# Acoustics_Board.net
KiCad netlist of a schematic drawn in Altium Designer
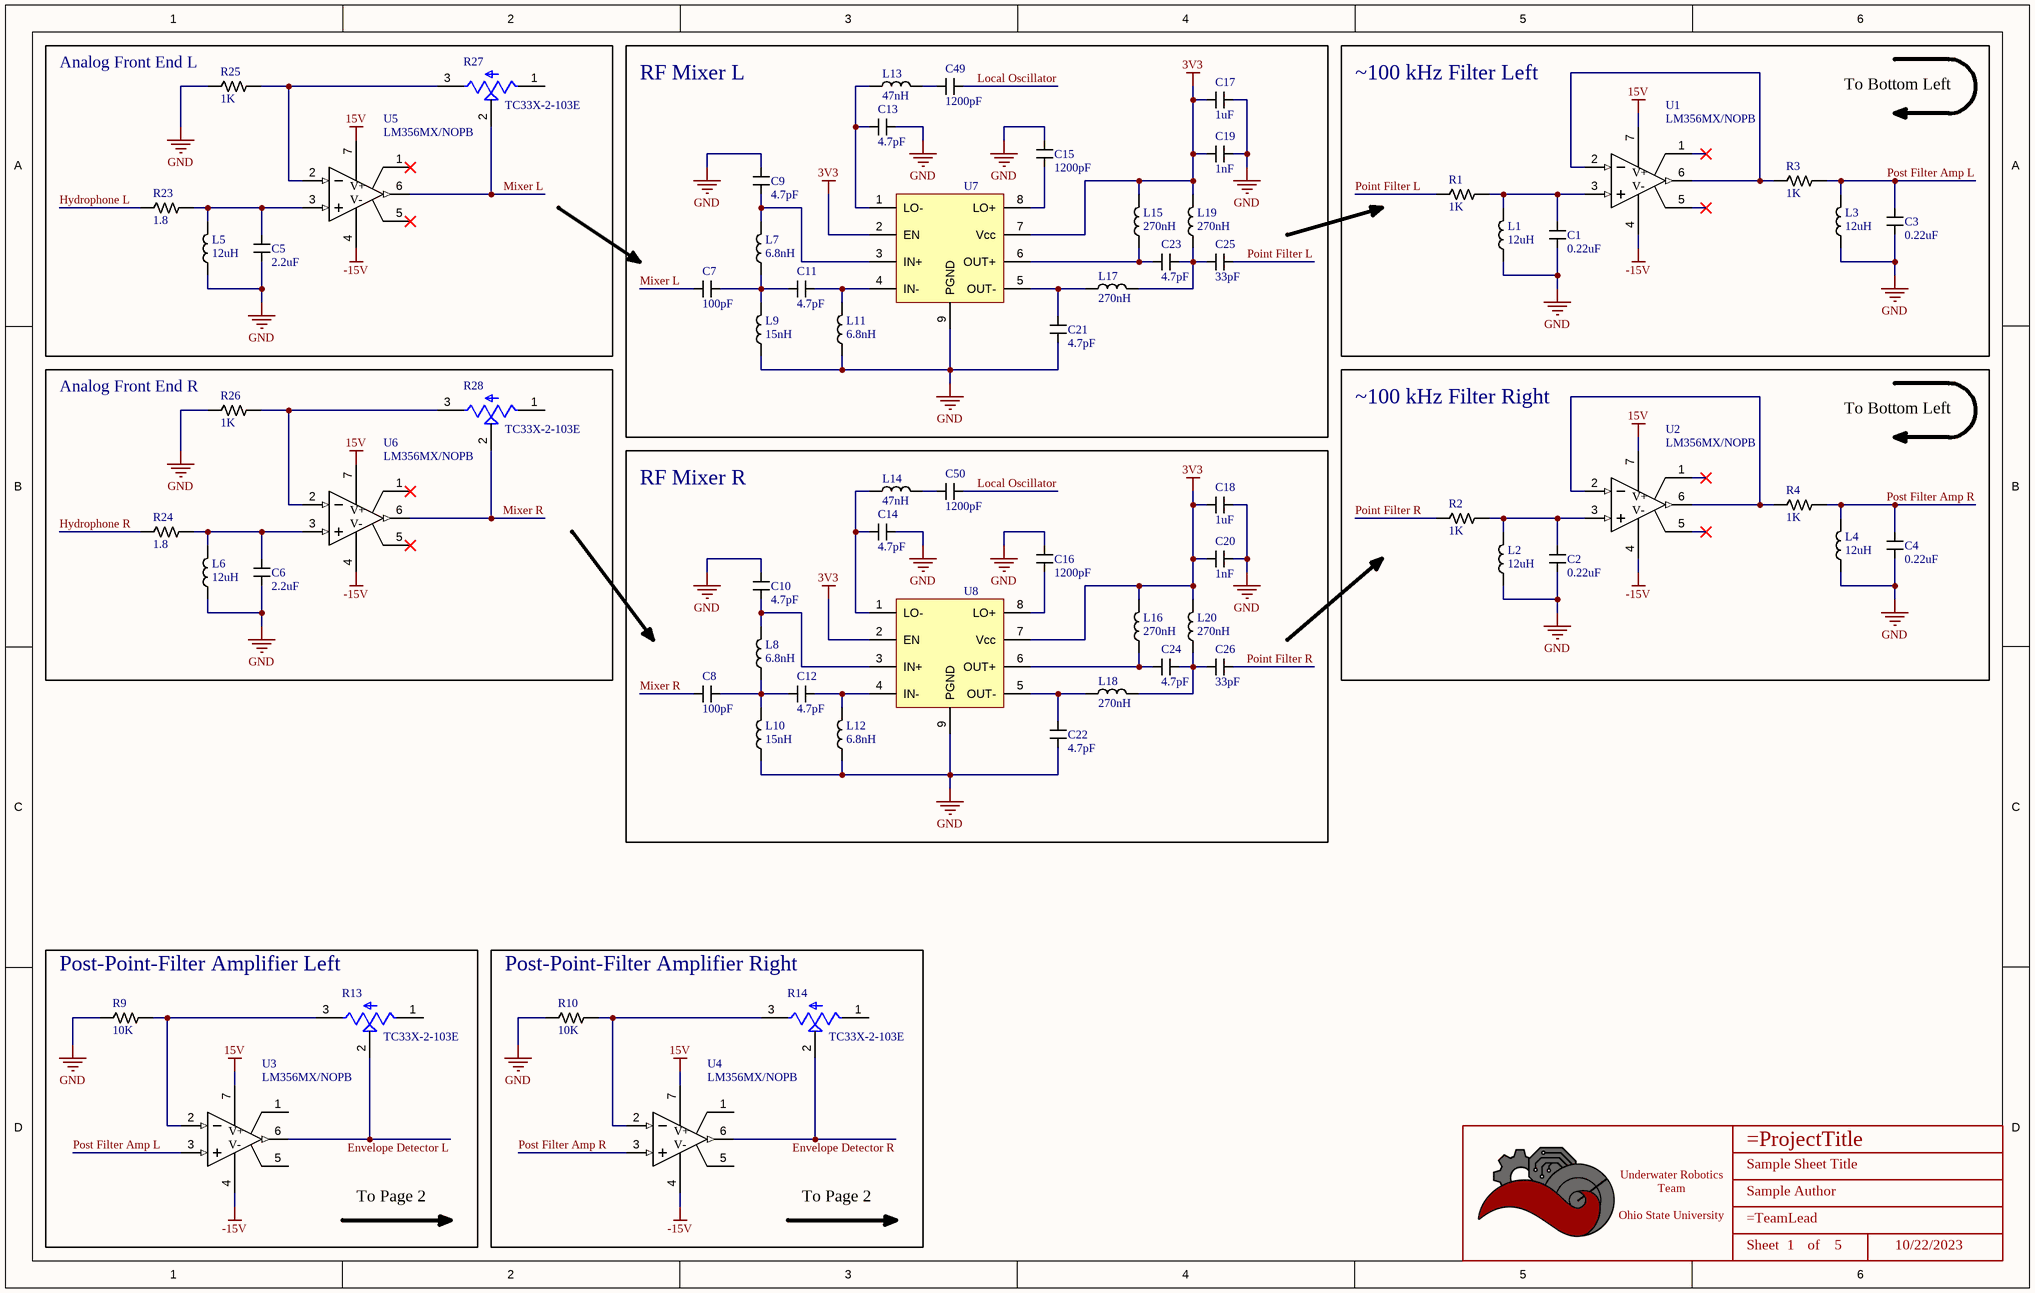
[diagram p0: Acoustics Board.SchDoc]

(export (version "E")
  (design (tool "Eeschema 10.0.6"))
  (components
    (comp (ref "*")
      (value "Title_Block")
      (footprint "LOGO")
      (description "UWRT Schematic Title Block Template\r\n\r\nCreated June 2021, Dylan Trainor")
      (libsource (lib "UWRT") (part "Title_Block"))
    )
    (comp (ref "C1")
      (value "0.22uF")
      (footprint "CAPACITOR_0603")
      (description "CAP CER 0.22uF 16V X7R 0603")
      (fields
        (field (name "TOLERANCE") "+/- 5%")
        (field (name "VOLTAGE") "16V")
        (field (name "MADE BY") "Nathan Ayer")
      )
      (libsource (lib "Capacitors") (part "CAPACITOR_0.000027uF_0603"))
    )
    (comp (ref "C2")
      (value "0.22uF")
      (footprint "CAPACITOR_0603")
      (description "CAP CER 0.22uF 16V X7R 0603")
      (fields
        (field (name "TOLERANCE") "+/- 5%")
        (field (name "VOLTAGE") "16V")
        (field (name "MADE BY") "Nathan Ayer")
      )
      (libsource (lib "Capacitors") (part "CAPACITOR_0.000027uF_0603"))
    )
    (comp (ref "C3")
      (value "0.22uF")
      (footprint "CAPACITOR_0603")
      (description "CAP CER 0.22uF 16V X7R 0603")
      (fields
        (field (name "TOLERANCE") "+/- 5%")
        (field (name "VOLTAGE") "16V")
        (field (name "MADE BY") "Nathan Ayer")
      )
      (libsource (lib "Capacitors") (part "CAPACITOR_0.000027uF_0603"))
    )
    (comp (ref "C4")
      (value "0.22uF")
      (footprint "CAPACITOR_0603")
      (description "CAP CER 0.22uF 16V X7R 0603")
      (fields
        (field (name "TOLERANCE") "+/- 5%")
        (field (name "VOLTAGE") "16V")
        (field (name "MADE BY") "Nathan Ayer")
      )
      (libsource (lib "Capacitors") (part "CAPACITOR_0.000027uF_0603"))
    )
    (comp (ref "C5")
      (value "2.2uF")
      (footprint "CAPACITOR_0603")
      (description "CAP CER 2.2PF 50V C0G/NP0 0603")
      (fields
        (field (name "TOLERANCE") "+/- 20%")
        (field (name "VOLTAGE") "6.3V")
        (field (name "MADE BY") "Flip B")
      )
      (libsource (lib "Capacitors") (part "CAPACITOR_22uF_0603"))
    )
    (comp (ref "C6")
      (value "2.2uF")
      (footprint "CAPACITOR_0603")
      (description "CAP CER 2.2PF 50V C0G/NP0 0603")
      (fields
        (field (name "TOLERANCE") "+/- 20%")
        (field (name "VOLTAGE") "6.3V")
        (field (name "MADE BY") "Flip B")
      )
      (libsource (lib "Capacitors") (part "CAPACITOR_22uF_0603"))
    )
    (comp (ref "C7")
      (value "100pF")
      (footprint "CAPACITOR_0402")
      (description "Cap 100pF 25V +/-10%\r\nCeramic 0402")
      (fields
        (field (name "TOLERANCE") "+/- 10%")
        (field (name "VOLTAGE") "25V")
        (field (name "MADE BY") "Robert Pafford")
      )
      (libsource (lib "Capacitors") (part "CAPACITOR_0.0001uF_0402"))
    )
    (comp (ref "C8")
      (value "100pF")
      (footprint "CAPACITOR_0402")
      (description "Cap 100pF 25V +/-10%\r\nCeramic 0402")
      (fields
        (field (name "TOLERANCE") "+/- 10%")
        (field (name "VOLTAGE") "25V")
        (field (name "MADE BY") "Robert Pafford")
      )
      (libsource (lib "Capacitors") (part "CAPACITOR_0.0001uF_0402"))
    )
    (comp (ref "C9")
      (value "4.7pF")
      (footprint "CAPACITOR_0402")
      (description "4.7 pF ±0.1pF 50V Ceramic Capacitor C0G, NP0 0402 (1005 Metric)")
      (fields (field (name "TOLERANCE") "+/- 0.1 pF") (field (name "VOLTAGE") "50V"))
      (libsource (lib "Capacitors") (part "CAPACITOR_0.000015uF_0402"))
    )
    (comp (ref "C10")
      (value "4.7pF")
      (footprint "CAPACITOR_0402")
      (description "4.7 pF ±0.1pF 50V Ceramic Capacitor C0G, NP0 0402 (1005 Metric)")
      (fields (field (name "TOLERANCE") "+/- 0.1 pF") (field (name "VOLTAGE") "50V"))
      (libsource (lib "Capacitors") (part "CAPACITOR_0.000015uF_0402"))
    )
    (comp (ref "C11")
      (value "4.7pF")
      (footprint "CAPACITOR_0402")
      (description "4.7 pF ±0.1pF 50V Ceramic Capacitor C0G, NP0 0402 (1005 Metric)")
      (fields (field (name "TOLERANCE") "+/- 0.1 pF") (field (name "VOLTAGE") "50V"))
      (libsource (lib "Capacitors") (part "CAPACITOR_0.000015uF_0402"))
    )
    (comp (ref "C12")
      (value "4.7pF")
      (footprint "CAPACITOR_0402")
      (description "4.7 pF ±0.1pF 50V Ceramic Capacitor C0G, NP0 0402 (1005 Metric)")
      (fields (field (name "TOLERANCE") "+/- 0.1 pF") (field (name "VOLTAGE") "50V"))
      (libsource (lib "Capacitors") (part "CAPACITOR_0.000015uF_0402"))
    )
    (comp (ref "C13")
      (value "4.7pF")
      (footprint "CAPACITOR_0402")
      (description "4.7 pF ±0.1pF 50V Ceramic Capacitor C0G, NP0 0402 (1005 Metric)")
      (fields (field (name "TOLERANCE") "+/- 0.1 pF") (field (name "VOLTAGE") "50V"))
      (libsource (lib "Capacitors") (part "CAPACITOR_0.000015uF_0402"))
    )
    (comp (ref "C14")
      (value "4.7pF")
      (footprint "CAPACITOR_0402")
      (description "4.7 pF ±0.1pF 50V Ceramic Capacitor C0G, NP0 0402 (1005 Metric)")
      (fields (field (name "TOLERANCE") "+/- 0.1 pF") (field (name "VOLTAGE") "50V"))
      (libsource (lib "Capacitors") (part "CAPACITOR_0.000015uF_0402"))
    )
    (comp (ref "C15")
      (value "1200pF")
      (footprint "CAPACITOR_0402")
      (description "CAP CER 1200PF 50V X7R 0402")
      (fields
        (field (name "TOLERANCE") "+/- 5%")
        (field (name "VOLTAGE") "50V")
        (field (name "MADE BY") "Robert Pafford")
      )
      (libsource (lib "Capacitors") (part "CAPACITOR_0.0012uF_0402"))
    )
    (comp (ref "C16")
      (value "1200pF")
      (footprint "CAPACITOR_0402")
      (description "CAP CER 1200PF 50V X7R 0402")
      (fields
        (field (name "TOLERANCE") "+/- 5%")
        (field (name "VOLTAGE") "50V")
        (field (name "MADE BY") "Robert Pafford")
      )
      (libsource (lib "Capacitors") (part "CAPACITOR_0.0012uF_0402"))
    )
    (comp (ref "C17")
      (value "1uF")
      (footprint "CAPACITOR_0603")
      (description "Cap 1uF 25V +/-10%\r\nCeramic 0603")
      (fields
        (field (name "TOLERANCE") "+/- 10%")
        (field (name "VOLTAGE") "16V")
        (field (name "MADE BY") "Flip B")
      )
      (libsource (lib "Capacitors") (part "CAPACITOR_1uF_0603_25V"))
    )
    (comp (ref "C18")
      (value "1uF")
      (footprint "CAPACITOR_0603")
      (description "Cap 1uF 25V +/-10%\r\nCeramic 0603")
      (fields
        (field (name "TOLERANCE") "+/- 10%")
        (field (name "VOLTAGE") "16V")
        (field (name "MADE BY") "Flip B")
      )
      (libsource (lib "Capacitors") (part "CAPACITOR_1uF_0603_25V"))
    )
    (comp (ref "C19")
      (value "1nF")
      (footprint "CAPACITOR_0603")
      (description "Cap 1000pF 50V +/-2%\r\nCeramic 0603")
      (fields
        (field (name "TOLERANCE") "+/- 2%")
        (field (name "VOLTAGE") "50")
        (field (name "MADE BY") "Flip B")
      )
      (libsource (lib "Capacitors") (part "CAPACITOR_0.001uF_0603"))
    )
    (comp (ref "C20")
      (value "1nF")
      (footprint "CAPACITOR_0603")
      (description "Cap 1000pF 50V +/-2%\r\nCeramic 0603")
      (fields
        (field (name "TOLERANCE") "+/- 2%")
        (field (name "VOLTAGE") "50")
        (field (name "MADE BY") "Flip B")
      )
      (libsource (lib "Capacitors") (part "CAPACITOR_0.001uF_0603"))
    )
    (comp (ref "C21")
      (value "4.7pF")
      (footprint "CAPACITOR_0402")
      (description "4.7 pF ±0.1pF 50V Ceramic Capacitor C0G, NP0 0402 (1005 Metric)")
      (fields (field (name "TOLERANCE") "+/- 0.1 pF") (field (name "VOLTAGE") "50V"))
      (libsource (lib "Capacitors") (part "CAPACITOR_0.000015uF_0402"))
    )
    (comp (ref "C22")
      (value "4.7pF")
      (footprint "CAPACITOR_0402")
      (description "4.7 pF ±0.1pF 50V Ceramic Capacitor C0G, NP0 0402 (1005 Metric)")
      (fields (field (name "TOLERANCE") "+/- 0.1 pF") (field (name "VOLTAGE") "50V"))
      (libsource (lib "Capacitors") (part "CAPACITOR_0.000015uF_0402"))
    )
    (comp (ref "C23")
      (value "4.7pF")
      (footprint "CAPACITOR_0402")
      (description "4.7 pF ±0.1pF 50V Ceramic Capacitor C0G, NP0 0402 (1005 Metric)")
      (fields (field (name "TOLERANCE") "+/- 0.1 pF") (field (name "VOLTAGE") "50V"))
      (libsource (lib "Capacitors") (part "CAPACITOR_0.000015uF_0402"))
    )
    (comp (ref "C24")
      (value "4.7pF")
      (footprint "CAPACITOR_0402")
      (description "4.7 pF ±0.1pF 50V Ceramic Capacitor C0G, NP0 0402 (1005 Metric)")
      (fields (field (name "TOLERANCE") "+/- 0.1 pF") (field (name "VOLTAGE") "50V"))
      (libsource (lib "Capacitors") (part "CAPACITOR_0.000015uF_0402"))
    )
    (comp (ref "C25")
      (value "33pF")
      (footprint "CAPACITOR_0603")
      (description "33 pF ±5% 250V Ceramic Capacitor C0G, NP0 0603 (1608 Metric)")
      (fields (field (name "TOLERANCE") "+/- 5%") (field (name "VOLTAGE") "250V"))
      (libsource (lib "Capacitors") (part "CAPACITOR_0.001uF_0603"))
    )
    (comp (ref "C26")
      (value "33pF")
      (footprint "CAPACITOR_0603")
      (description "33 pF ±5% 250V Ceramic Capacitor C0G, NP0 0603 (1608 Metric)")
      (fields (field (name "TOLERANCE") "+/- 5%") (field (name "VOLTAGE") "250V"))
      (libsource (lib "Capacitors") (part "CAPACITOR_0.001uF_0603"))
    )
    (comp (ref "C49")
      (value "1200pF")
      (footprint "CAPACITOR_0402")
      (description "CAP CER 1200PF 50V X7R 0402")
      (fields
        (field (name "TOLERANCE") "+/- 5%")
        (field (name "VOLTAGE") "50V")
        (field (name "MADE BY") "Robert Pafford")
      )
      (libsource (lib "Capacitors") (part "CAPACITOR_0.0012uF_0402"))
    )
    (comp (ref "C50")
      (value "1200pF")
      (footprint "CAPACITOR_0402")
      (description "CAP CER 1200PF 50V X7R 0402")
      (fields
        (field (name "TOLERANCE") "+/- 5%")
        (field (name "VOLTAGE") "50V")
        (field (name "MADE BY") "Robert Pafford")
      )
      (libsource (lib "Capacitors") (part "CAPACITOR_0.0012uF_0402"))
    )
    (comp (ref "L1")
      (value "12uH")
      (footprint "INDUCTOR_0603")
      (description "12 µH Shielded Multilayer Inductor 10 mA 1.8Ohm Max 0603 (1608 Metric)")
      (fields
        (field (name "TOLERANCE") "+/- 5%")
        (field (name "Comment") "FIXED IND 12UH 10MA 1.8 OHM SMD")
        (field (name "MADE BY") "Nathan Ayer")
      )
      (libsource (lib "Inductors") (part "INDUCTOR_12uH_0603"))
    )
    (comp (ref "L2")
      (value "12uH")
      (footprint "INDUCTOR_0603")
      (description "12 µH Shielded Multilayer Inductor 10 mA 1.8Ohm Max 0603 (1608 Metric)")
      (fields
        (field (name "TOLERANCE") "+/- 5%")
        (field (name "Comment") "FIXED IND 12UH 10MA 1.8 OHM SMD")
        (field (name "MADE BY") "Nathan Ayer")
      )
      (libsource (lib "Inductors") (part "INDUCTOR_12uH_0603"))
    )
    (comp (ref "L3")
      (value "12uH")
      (footprint "INDUCTOR_0603")
      (description "12 µH Shielded Multilayer Inductor 10 mA 1.8Ohm Max 0603 (1608 Metric)")
      (fields
        (field (name "TOLERANCE") "+/- 5%")
        (field (name "Comment") "FIXED IND 12UH 10MA 1.8 OHM SMD")
        (field (name "MADE BY") "Nathan Ayer")
      )
      (libsource (lib "Inductors") (part "INDUCTOR_12uH_0603"))
    )
    (comp (ref "L4")
      (value "12uH")
      (footprint "INDUCTOR_0603")
      (description "12 µH Shielded Multilayer Inductor 10 mA 1.8Ohm Max 0603 (1608 Metric)")
      (fields
        (field (name "TOLERANCE") "+/- 5%")
        (field (name "Comment") "FIXED IND 12UH 10MA 1.8 OHM SMD")
        (field (name "MADE BY") "Nathan Ayer")
      )
      (libsource (lib "Inductors") (part "INDUCTOR_12uH_0603"))
    )
    (comp (ref "L5")
      (value "12uH")
      (footprint "INDUCTOR_0603")
      (description "12 µH Shielded Multilayer Inductor 10 mA 1.8Ohm Max 0603 (1608 Metric)")
      (fields
        (field (name "TOLERANCE") "+/- 20%")
        (field (name "Comment") "FIXED IND 12UH 10MA 1.8 OHM SMD")
        (field (name "MADE BY") "Robert Pafford")
      )
      (libsource (lib "Inductors") (part "INDUCTOR_12uH_0603"))
    )
    (comp (ref "L6")
      (value "12uH")
      (footprint "INDUCTOR_0603")
      (description "12 µH Shielded Multilayer Inductor 10 mA 1.8Ohm Max 0603 (1608 Metric)")
      (fields
        (field (name "TOLERANCE") "+/- 20%")
        (field (name "Comment") "FIXED IND 12UH 10MA 1.8 OHM SMD")
        (field (name "MADE BY") "Robert Pafford")
      )
      (libsource (lib "Inductors") (part "INDUCTOR_12uH_0603"))
    )
    (comp (ref "L7")
      (value "6.8nH")
      (footprint "INDUCTOR_0402")
      (description "6.8 nH Unshielded Multilayer Inductor 250 mA 320mOhm Max 0402 (1005 Metric)")
      (fields (field (name "TOLERANCE") "+/- 5%") (field (name "Comment") "FIXED IND 6.8NH 250MA 320MOHM SM"))
      (libsource (lib "Inductors") (part "INDUCTOR_15nH_0402"))
    )
    (comp (ref "L8")
      (value "6.8nH")
      (footprint "INDUCTOR_0402")
      (description "6.8 nH Unshielded Multilayer Inductor 250 mA 320mOhm Max 0402 (1005 Metric)")
      (fields (field (name "TOLERANCE") "+/- 5%") (field (name "Comment") "FIXED IND 6.8NH 250MA 320MOHM SM"))
      (libsource (lib "Inductors") (part "INDUCTOR_15nH_0402"))
    )
    (comp (ref "L9")
      (value "15nH")
      (footprint "INDUCTOR_0402")
      (description "15 nH Unshielded Multilayer Inductor 250 mA 600mOhm Max 0402 (1005 Metric)")
      (fields (field (name "TOLERANCE") "+/- 5%") (field (name "Comment") "FIXED IND 15NH 250MA 600MOHM SMD"))
      (libsource (lib "Inductors") (part "INDUCTOR_15nH_0402"))
    )
    (comp (ref "L10")
      (value "15nH")
      (footprint "INDUCTOR_0402")
      (description "15 nH Unshielded Multilayer Inductor 250 mA 600mOhm Max 0402 (1005 Metric)")
      (fields (field (name "TOLERANCE") "+/- 5%") (field (name "Comment") "FIXED IND 15NH 250MA 600MOHM SMD"))
      (libsource (lib "Inductors") (part "INDUCTOR_15nH_0402"))
    )
    (comp (ref "L11")
      (value "6.8nH")
      (footprint "INDUCTOR_0402")
      (description "6.8 nH Unshielded Multilayer Inductor 250 mA 320mOhm Max 0402 (1005 Metric)")
      (fields (field (name "TOLERANCE") "+/- 5%") (field (name "Comment") "FIXED IND 6.8NH 250MA 320MOHM SM"))
      (libsource (lib "Inductors") (part "INDUCTOR_15nH_0402"))
    )
    (comp (ref "L12")
      (value "6.8nH")
      (footprint "INDUCTOR_0402")
      (description "6.8 nH Unshielded Multilayer Inductor 250 mA 320mOhm Max 0402 (1005 Metric)")
      (fields (field (name "TOLERANCE") "+/- 5%") (field (name "Comment") "FIXED IND 6.8NH 250MA 320MOHM SM"))
      (libsource (lib "Inductors") (part "INDUCTOR_15nH_0402"))
    )
    (comp (ref "L13")
      (value "47nH")
      (footprint "INDUCTOR_0402")
      (description "47 nH Unshielded Multilayer Inductor 200 mA 1.1Ohm Max 0402 (1005 Metric)")
      (fields (field (name "TOLERANCE") "+/- 5%") (field (name "Comment") "FIXED IND 47NH 200MA 1.1 OHM SMD"))
      (libsource (lib "Inductors") (part "INDUCTOR_15nH_0402"))
    )
    (comp (ref "L14")
      (value "47nH")
      (footprint "INDUCTOR_0402")
      (description "47 nH Unshielded Multilayer Inductor 200 mA 1.1Ohm Max 0402 (1005 Metric)")
      (fields (field (name "TOLERANCE") "+/- 5%") (field (name "Comment") "FIXED IND 47NH 200MA 1.1 OHM SMD"))
      (libsource (lib "Inductors") (part "INDUCTOR_15nH_0402"))
    )
    (comp (ref "L15")
      (value "270nH")
      (footprint "INDUCTOR_0402")
      (description "270 nH Unshielded Multilayer Inductor 110 mA 4.94Ohm Max 0402 (1005 Metric)")
      (fields
        (field (name "TOLERANCE") "+/- 10%")
        (field (name "Comment") "FIXED IND 270NH 110MA 4.94OHM SM")
      )
      (libsource (lib "Inductors") (part "INDUCTOR_15nH_0402"))
    )
    (comp (ref "L16")
      (value "270nH")
      (footprint "INDUCTOR_0402")
      (description "270 nH Unshielded Multilayer Inductor 110 mA 4.94Ohm Max 0402 (1005 Metric)")
      (fields
        (field (name "TOLERANCE") "+/- 10%")
        (field (name "Comment") "FIXED IND 270NH 110MA 4.94OHM SM")
      )
      (libsource (lib "Inductors") (part "INDUCTOR_15nH_0402"))
    )
    (comp (ref "L17")
      (value "270nH")
      (footprint "INDUCTOR_0402")
      (description "270 nH Unshielded Multilayer Inductor 110 mA 4.94Ohm Max 0402 (1005 Metric)")
      (fields
        (field (name "TOLERANCE") "+/- 10%")
        (field (name "Comment") "FIXED IND 270NH 110MA 4.94OHM SM")
      )
      (libsource (lib "Inductors") (part "INDUCTOR_15nH_0402"))
    )
    (comp (ref "L18")
      (value "270nH")
      (footprint "INDUCTOR_0402")
      (description "270 nH Unshielded Multilayer Inductor 110 mA 4.94Ohm Max 0402 (1005 Metric)")
      (fields
        (field (name "TOLERANCE") "+/- 10%")
        (field (name "Comment") "FIXED IND 270NH 110MA 4.94OHM SM")
      )
      (libsource (lib "Inductors") (part "INDUCTOR_15nH_0402"))
    )
    (comp (ref "L19")
      (value "270nH")
      (footprint "INDUCTOR_0402")
      (description "270 nH Unshielded Multilayer Inductor 110 mA 4.94Ohm Max 0402 (1005 Metric)")
      (fields
        (field (name "TOLERANCE") "+/- 10%")
        (field (name "Comment") "FIXED IND 270NH 110MA 4.94OHM SM")
      )
      (libsource (lib "Inductors") (part "INDUCTOR_15nH_0402"))
    )
    (comp (ref "L20")
      (value "270nH")
      (footprint "INDUCTOR_0402")
      (description "270 nH Unshielded Multilayer Inductor 110 mA 4.94Ohm Max 0402 (1005 Metric)")
      (fields
        (field (name "TOLERANCE") "+/- 10%")
        (field (name "Comment") "FIXED IND 270NH 110MA 4.94OHM SM")
      )
      (libsource (lib "Inductors") (part "INDUCTOR_15nH_0402"))
    )
    (comp (ref "R1")
      (value "1.45k Ohm 0.1% 1/10W")
      (footprint "RESISTOR_0603")
      (description "RES 1.45K OHM 0.1% 1/10W 0603")
      (fields
        (field (name "TOLERANCE") "+/- 0.1%")
        (field (name "VALUE  (OHMS)") "1K")
        (field (name "MADE BY") "Nathan Ayer")
      )
      (libsource (lib "Resistors") (part "RESISTOR_1K_0603"))
    )
    (comp (ref "R2")
      (value "1.45k Ohm 0.1% 1/10W")
      (footprint "RESISTOR_0603")
      (description "RES 1.45K OHM 0.1% 1/10W 0603")
      (fields
        (field (name "TOLERANCE") "+/- 0.1%")
        (field (name "VALUE  (OHMS)") "1K")
        (field (name "MADE BY") "Nathan Ayer")
      )
      (libsource (lib "Resistors") (part "RESISTOR_1K_0603"))
    )
    (comp (ref "R3")
      (value "1.45k Ohm 0.1% 1/10W")
      (footprint "RESISTOR_0603")
      (description "RES 1.45K OHM 0.1% 1/10W 0603")
      (fields
        (field (name "TOLERANCE") "+/- 0.1%")
        (field (name "VALUE  (OHMS)") "1K")
        (field (name "MADE BY") "Nathan Ayer")
      )
      (libsource (lib "Resistors") (part "RESISTOR_1K_0603"))
    )
    (comp (ref "R4")
      (value "1.45k Ohm 0.1% 1/10W")
      (footprint "RESISTOR_0603")
      (description "RES 1.45K OHM 0.1% 1/10W 0603")
      (fields
        (field (name "TOLERANCE") "+/- 0.1%")
        (field (name "VALUE  (OHMS)") "1K")
        (field (name "MADE BY") "Nathan Ayer")
      )
      (libsource (lib "Resistors") (part "RESISTOR_1K_0603"))
    )
    (comp (ref "R9")
      (value "10k Ohm 0.5% 1/10W")
      (footprint "RESISTOR_0603")
      (description "RES 10k OHM 0.5% 1/10W 0603")
      (fields
        (field (name "TOLERANCE") "+/- 0.5%")
        (field (name "VALUE  (OHMS)") "10K")
        (field (name "MADE BY") "Robert Pafford")
      )
      (libsource (lib "Resistors") (part "RESISTOR_10K_0.5%_0603"))
    )
    (comp (ref "R10")
      (value "10k Ohm 0.5% 1/10W")
      (footprint "RESISTOR_0603")
      (description "RES 10k OHM 0.5% 1/10W 0603")
      (fields
        (field (name "TOLERANCE") "+/- 0.5%")
        (field (name "VALUE  (OHMS)") "10K")
        (field (name "MADE BY") "Robert Pafford")
      )
      (libsource (lib "Resistors") (part "RESISTOR_10K_0.5%_0603"))
    )
    (comp (ref "R13")
      (value "TC33X-2-103E")
      (footprint "TRIM_TC33X-2-203E")
      (description "20 kOhms 0.1W, 1/10W J Lead Surface Mount Trimmer Potentiometer Cermet 1 Turn Top Adjustment")
      (fields (field (name "MF") "Bourns") (field (name "DIGI-KEY_PART_NUMBER") "TC33X-2-203ECT-ND"))
      (libsource (lib "Resistors") (part "TC33X-2-203E"))
    )
    (comp (ref "R14")
      (value "TC33X-2-103E")
      (footprint "TRIM_TC33X-2-203E")
      (description "20 kOhms 0.1W, 1/10W J Lead Surface Mount Trimmer Potentiometer Cermet 1 Turn Top Adjustment")
      (fields (field (name "MF") "Bourns") (field (name "DIGI-KEY_PART_NUMBER") "TC33X-2-203ECT-ND"))
      (libsource (lib "Resistors") (part "TC33X-2-203E"))
    )
    (comp (ref "R23")
      (value "2k Ohm 1% 1/16W")
      (footprint "RESISTOR_0402")
      (description "RES 2k OHM 1% 1/16W 0402")
      (fields
        (field (name "TOLERANCE") "+/- 1%")
        (field (name "VALUE  (OHMS)") "1.8")
        (field (name "MADE BY") "Flip B")
      )
      (libsource (lib "Resistors") (part "RESISTOR_2K_0402"))
    )
    (comp (ref "R24")
      (value "2k Ohm 1% 1/16W")
      (footprint "RESISTOR_0402")
      (description "RES 2k OHM 1% 1/16W 0402")
      (fields
        (field (name "TOLERANCE") "+/- 1%")
        (field (name "VALUE  (OHMS)") "1.8")
        (field (name "MADE BY") "Flip B")
      )
      (libsource (lib "Resistors") (part "RESISTOR_2K_0402"))
    )
    (comp (ref "R25")
      (value "1k Ohm 5% 1/8W")
      (footprint "RESISTOR_0603")
      (description "RES 1.8 OHM 5% 1/8W 0603")
      (fields
        (field (name "TOLERANCE") "+/- 5%")
        (field (name "VALUE  (OHMS)") "1K")
        (field (name "MADE BY") "Robert Pafford")
      )
      (libsource (lib "Resistors") (part "RESISTOR_1K_0603"))
    )
    (comp (ref "R26")
      (value "1k Ohm 5% 1/8W")
      (footprint "RESISTOR_0603")
      (description "RES 1k OHM 5% 1/8W 0603")
      (fields
        (field (name "TOLERANCE") "+/- 5%")
        (field (name "VALUE  (OHMS)") "1K")
        (field (name "MADE BY") "Robert Pafford")
      )
      (libsource (lib "Resistors") (part "RESISTOR_1K_0603"))
    )
    (comp (ref "R27")
      (value "TC33X-2-103E")
      (footprint "TRIM_TC33X-2-203E")
      (description "20 kOhms 0.1W, 1/10W J Lead Surface Mount Trimmer Potentiometer Cermet 1 Turn Top Adjustment")
      (fields (field (name "MF") "Bourns") (field (name "DIGI-KEY_PART_NUMBER") "TC33X-2-203ECT-ND"))
      (libsource (lib "Resistors") (part "TC33X-2-203E"))
    )
    (comp (ref "R28")
      (value "TC33X-2-103E")
      (footprint "TRIM_TC33X-2-203E")
      (description "20 kOhms 0.1W, 1/10W J Lead Surface Mount Trimmer Potentiometer Cermet 1 Turn Top Adjustment")
      (fields (field (name "MF") "Bourns") (field (name "DIGI-KEY_PART_NUMBER") "TC33X-2-203ECT-ND"))
      (libsource (lib "Resistors") (part "TC33X-2-203E"))
    )
    (comp (ref "U1")
      (value "LM356MX/NOPB")
      (footprint "SOIC-8")
      (description "IC OPAMP JFET 1 CIRCUIT 8SOIC")
      (fields
        (field (name "PARTNUMBER") "LM8261M5X/NOPB")
        (field (name "MANUFACTURER") "Texas Instruments")
        (field (name "CREATED BY") "Dylan T")
      )
      (libsource (lib "Integrated Circuits") (part "LM356MX/NOPB"))
    )
    (comp (ref "U2")
      (value "LM356MX/NOPB")
      (footprint "SOIC-8")
      (description "IC OPAMP JFET 1 CIRCUIT 8SOIC")
      (fields
        (field (name "PARTNUMBER") "LM8261M5X/NOPB")
        (field (name "MANUFACTURER") "Texas Instruments")
        (field (name "CREATED BY") "Dylan T")
      )
      (libsource (lib "Integrated Circuits") (part "LM356MX/NOPB"))
    )
    (comp (ref "U3")
      (value "LM356MX/NOPB")
      (footprint "SOIC-8")
      (description "IC OPAMP JFET 1 CIRCUIT 8SOIC")
      (fields
        (field (name "PARTNUMBER") "LM8261M5X/NOPB")
        (field (name "MANUFACTURER") "Texas Instruments")
        (field (name "CREATED BY") "Dylan T")
      )
      (libsource (lib "Integrated Circuits") (part "LM356MX/NOPB"))
    )
    (comp (ref "U4")
      (value "LM356MX/NOPB")
      (footprint "SOIC-8")
      (description "IC OPAMP JFET 1 CIRCUIT 8SOIC")
      (fields
        (field (name "PARTNUMBER") "LM8261M5X/NOPB")
        (field (name "MANUFACTURER") "Texas Instruments")
        (field (name "CREATED BY") "Dylan T")
      )
      (libsource (lib "Integrated Circuits") (part "LM356MX/NOPB"))
    )
    (comp (ref "U5")
      (value "LM356MX/NOPB")
      (footprint "SOIC-8")
      (description "IC OPAMP JFET 1 CIRCUIT 8SOIC")
      (fields
        (field (name "PARTNUMBER") "LM8261M5X/NOPB")
        (field (name "MANUFACTURER") "Texas Instruments")
        (field (name "CREATED BY") "Dylan T")
      )
      (libsource (lib "Integrated Circuits") (part "LM356MX/NOPB"))
    )
    (comp (ref "U6")
      (value "LM356MX/NOPB")
      (footprint "SOIC-8")
      (description "IC OPAMP JFET 1 CIRCUIT 8SOIC")
      (fields
        (field (name "PARTNUMBER") "LM8261M5X/NOPB")
        (field (name "MANUFACTURER") "Texas Instruments")
        (field (name "CREATED BY") "Dylan T")
      )
      (libsource (lib "Integrated Circuits") (part "LM356MX/NOPB"))
    )
    (comp (ref "U7")
      (value "LT5560EDD")
      (footprint "LT5560EDD")
      (description "RF Mixer IC CATV, DBS, PHS, UHF, VHF Up/Down Converter 10kHz ~ 4GHz 8-DFN (3x3)")
      (libsource (lib "Integrated Circuits") (part "LT5560EDD"))
    )
    (comp (ref "U8")
      (value "LT5560EDD")
      (footprint "LT5560EDD")
      (description "RF Mixer IC CATV, DBS, PHS, UHF, VHF Up/Down Converter 10kHz ~ 4GHz 8-DFN (3x3)")
      (libsource (lib "Integrated Circuits") (part "LT5560EDD"))
    )
  )
  (nets
    (net (code "1") (name "-15V") (class "Default")
      (node (ref "U1") (pin "4") (pinfunction "V-_4") (pintype "power_in"))
      (node (ref "U2") (pin "4") (pinfunction "V-_4") (pintype "power_in"))
      (node (ref "U3") (pin "4") (pinfunction "V-_4") (pintype "power_in"))
      (node (ref "U4") (pin "4") (pinfunction "V-_4") (pintype "power_in"))
      (node (ref "U5") (pin "4") (pinfunction "V-_4") (pintype "power_in"))
      (node (ref "U6") (pin "4") (pinfunction "V-_4") (pintype "power_in"))
    )
    (net (code "2") (name "/Envelope Detector L") (class "Default")
      (node (ref "R13") (pin "2") (pinfunction "W_2") (pintype "passive"))
      (node (ref "U3") (pin "6") (pinfunction "OUT_6") (pintype "output"))
    )
    (net (code "3") (name "/Envelope Detector R") (class "Default")
      (node (ref "R14") (pin "2") (pinfunction "W_2") (pintype "passive"))
      (node (ref "U4") (pin "6") (pinfunction "OUT_6") (pintype "output"))
    )
    (net (code "4") (name "/Hydrophone L") (class "Default")
      (node (ref "R23") (pin "2") (pinfunction "2_2") (pintype "passive"))
    )
    (net (code "5") (name "/Hydrophone R") (class "Default")
      (node (ref "R24") (pin "2") (pinfunction "2_2") (pintype "passive"))
    )
    (net (code "6") (name "/Local Oscillator") (class "Default")
      (node (ref "C49") (pin "1") (pinfunction "1_1") (pintype "passive"))
      (node (ref "C50") (pin "1") (pinfunction "1_1") (pintype "passive"))
    )
    (net (code "7") (name "/Mixer L") (class "Default")
      (node (ref "C7") (pin "1") (pinfunction "1_1") (pintype "passive"))
      (node (ref "R27") (pin "2") (pinfunction "W_2") (pintype "passive"))
      (node (ref "U5") (pin "6") (pinfunction "OUT_6") (pintype "output"))
    )
    (net (code "8") (name "/Mixer R") (class "Default")
      (node (ref "C8") (pin "1") (pinfunction "1_1") (pintype "passive"))
      (node (ref "R28") (pin "2") (pinfunction "W_2") (pintype "passive"))
      (node (ref "U6") (pin "6") (pinfunction "OUT_6") (pintype "output"))
    )
    (net (code "9") (name "/Point Filter L") (class "Default")
      (node (ref "C25") (pin "1") (pinfunction "1_1") (pintype "passive"))
      (node (ref "R1") (pin "2") (pinfunction "2_2") (pintype "passive"))
    )
    (net (code "10") (name "/Point Filter R") (class "Default")
      (node (ref "C26") (pin "1") (pinfunction "1_1") (pintype "passive"))
      (node (ref "R2") (pin "2") (pinfunction "2_2") (pintype "passive"))
    )
    (net (code "11") (name "/Post Filter Amp L") (class "Default")
      (node (ref "C3") (pin "1") (pinfunction "1_1") (pintype "passive"))
      (node (ref "L3") (pin "1") (pinfunction "1_1") (pintype "passive"))
      (node (ref "R3") (pin "1") (pinfunction "1_1") (pintype "passive"))
      (node (ref "U3") (pin "3") (pinfunction "IN+_3") (pintype "input"))
    )
    (net (code "12") (name "/Post Filter Amp R") (class "Default")
      (node (ref "C4") (pin "1") (pinfunction "1_1") (pintype "passive"))
      (node (ref "L4") (pin "1") (pinfunction "1_1") (pintype "passive"))
      (node (ref "R4") (pin "1") (pinfunction "1_1") (pintype "passive"))
      (node (ref "U4") (pin "3") (pinfunction "IN+_3") (pintype "input"))
    )
    (net (code "13") (name "3V3") (class "Default")
      (node (ref "C17") (pin "2") (pinfunction "2_2") (pintype "passive"))
      (node (ref "C18") (pin "2") (pinfunction "2_2") (pintype "passive"))
      (node (ref "C19") (pin "2") (pinfunction "2_2") (pintype "passive"))
      (node (ref "C20") (pin "2") (pinfunction "2_2") (pintype "passive"))
      (node (ref "L15") (pin "1") (pinfunction "1_1") (pintype "passive"))
      (node (ref "L16") (pin "1") (pinfunction "1_1") (pintype "passive"))
      (node (ref "L19") (pin "1") (pinfunction "1_1") (pintype "passive"))
      (node (ref "L20") (pin "1") (pinfunction "1_1") (pintype "passive"))
      (node (ref "U7") (pin "2") (pinfunction "EN_2") (pintype "passive"))
      (node (ref "U7") (pin "7") (pinfunction "Vcc_7") (pintype "passive"))
      (node (ref "U8") (pin "2") (pinfunction "EN_2") (pintype "passive"))
      (node (ref "U8") (pin "7") (pinfunction "Vcc_7") (pintype "passive"))
    )
    (net (code "14") (name "15V") (class "Default")
      (node (ref "U1") (pin "7") (pinfunction "V+_7") (pintype "power_in"))
      (node (ref "U2") (pin "7") (pinfunction "V+_7") (pintype "power_in"))
      (node (ref "U3") (pin "7") (pinfunction "V+_7") (pintype "power_in"))
      (node (ref "U4") (pin "7") (pinfunction "V+_7") (pintype "power_in"))
      (node (ref "U5") (pin "7") (pinfunction "V+_7") (pintype "power_in"))
      (node (ref "U6") (pin "7") (pinfunction "V+_7") (pintype "power_in"))
    )
    (net (code "15") (name "GND") (class "Default")
      (node (ref "C1") (pin "2") (pinfunction "2_2") (pintype "passive"))
      (node (ref "C10") (pin "1") (pinfunction "1_1") (pintype "passive"))
      (node (ref "C13") (pin "1") (pinfunction "1_1") (pintype "passive"))
      (node (ref "C14") (pin "1") (pinfunction "1_1") (pintype "passive"))
      (node (ref "C15") (pin "1") (pinfunction "1_1") (pintype "passive"))
      (node (ref "C16") (pin "1") (pinfunction "1_1") (pintype "passive"))
      (node (ref "C17") (pin "1") (pinfunction "1_1") (pintype "passive"))
      (node (ref "C18") (pin "1") (pinfunction "1_1") (pintype "passive"))
      (node (ref "C19") (pin "1") (pinfunction "1_1") (pintype "passive"))
      (node (ref "C2") (pin "2") (pinfunction "2_2") (pintype "passive"))
      (node (ref "C20") (pin "1") (pinfunction "1_1") (pintype "passive"))
      (node (ref "C21") (pin "2") (pinfunction "2_2") (pintype "passive"))
      (node (ref "C22") (pin "2") (pinfunction "2_2") (pintype "passive"))
      (node (ref "C3") (pin "2") (pinfunction "2_2") (pintype "passive"))
      (node (ref "C4") (pin "2") (pinfunction "2_2") (pintype "passive"))
      (node (ref "C5") (pin "2") (pinfunction "2_2") (pintype "passive"))
      (node (ref "C6") (pin "2") (pinfunction "2_2") (pintype "passive"))
      (node (ref "C9") (pin "1") (pinfunction "1_1") (pintype "passive"))
      (node (ref "L1") (pin "2") (pinfunction "2_2") (pintype "passive"))
      (node (ref "L10") (pin "2") (pinfunction "2_2") (pintype "passive"))
      (node (ref "L11") (pin "2") (pinfunction "2_2") (pintype "passive"))
      (node (ref "L12") (pin "2") (pinfunction "2_2") (pintype "passive"))
      (node (ref "L2") (pin "2") (pinfunction "2_2") (pintype "passive"))
      (node (ref "L3") (pin "2") (pinfunction "2_2") (pintype "passive"))
      (node (ref "L4") (pin "2") (pinfunction "2_2") (pintype "passive"))
      (node (ref "L5") (pin "2") (pinfunction "2_2") (pintype "passive"))
      (node (ref "L6") (pin "2") (pinfunction "2_2") (pintype "passive"))
      (node (ref "L9") (pin "2") (pinfunction "2_2") (pintype "passive"))
      (node (ref "R10") (pin "2") (pinfunction "2_2") (pintype "passive"))
      (node (ref "R25") (pin "2") (pinfunction "2_2") (pintype "passive"))
      (node (ref "R26") (pin "2") (pinfunction "2_2") (pintype "passive"))
      (node (ref "R9") (pin "2") (pinfunction "2_2") (pintype "passive"))
      (node (ref "U7") (pin "9") (pinfunction "PGND_9") (pintype "passive"))
      (node (ref "U8") (pin "9") (pinfunction "PGND_9") (pintype "passive"))
    )
    (net (code "16") (name "Net-(C11-Pad2)") (class "Default")
      (node (ref "C11") (pin "2") (pinfunction "2_2") (pintype "passive"))
      (node (ref "C7") (pin "2") (pinfunction "2_2") (pintype "passive"))
      (node (ref "L7") (pin "2") (pinfunction "2_2") (pintype "passive"))
      (node (ref "L9") (pin "1") (pinfunction "1_1") (pintype "passive"))
    )
    (net (code "17") (name "Net-(C12-Pad2)") (class "Default")
      (node (ref "C12") (pin "2") (pinfunction "2_2") (pintype "passive"))
      (node (ref "C8") (pin "2") (pinfunction "2_2") (pintype "passive"))
      (node (ref "L10") (pin "1") (pinfunction "1_1") (pintype "passive"))
      (node (ref "L8") (pin "2") (pinfunction "2_2") (pintype "passive"))
    )
    (net (code "18") (name "Net-(C23-Pad1)") (class "Default")
      (node (ref "C23") (pin "1") (pinfunction "1_1") (pintype "passive"))
      (node (ref "C25") (pin "2") (pinfunction "2_2") (pintype "passive"))
      (node (ref "L17") (pin "1") (pinfunction "1_1") (pintype "passive"))
      (node (ref "L19") (pin "2") (pinfunction "2_2") (pintype "passive"))
    )
    (net (code "19") (name "Net-(C24-Pad1)") (class "Default")
      (node (ref "C24") (pin "1") (pinfunction "1_1") (pintype "passive"))
      (node (ref "C26") (pin "2") (pinfunction "2_2") (pintype "passive"))
      (node (ref "L18") (pin "1") (pinfunction "1_1") (pintype "passive"))
      (node (ref "L20") (pin "2") (pinfunction "2_2") (pintype "passive"))
    )
    (net (code "20") (name "Net-(C49-Pad2)") (class "Default")
      (node (ref "C49") (pin "2") (pinfunction "2_2") (pintype "passive"))
      (node (ref "L13") (pin "1") (pinfunction "1_1") (pintype "passive"))
    )
    (net (code "21") (name "Net-(C50-Pad2)") (class "Default")
      (node (ref "C50") (pin "2") (pinfunction "2_2") (pintype "passive"))
      (node (ref "L14") (pin "1") (pinfunction "1_1") (pintype "passive"))
    )
    (net (code "22") (name "Net-(R13-CW)") (class "Default")
      (node (ref "R13") (pin "3") (pinfunction "CW_3") (pintype "passive"))
      (node (ref "R9") (pin "1") (pinfunction "1_1") (pintype "passive"))
      (node (ref "U3") (pin "2") (pinfunction "IN-_2") (pintype "input"))
    )
    (net (code "23") (name "Net-(R14-CW)") (class "Default")
      (node (ref "R10") (pin "1") (pinfunction "1_1") (pintype "passive"))
      (node (ref "R14") (pin "3") (pinfunction "CW_3") (pintype "passive"))
      (node (ref "U4") (pin "2") (pinfunction "IN-_2") (pintype "input"))
    )
    (net (code "24") (name "Net-(R27-CW)") (class "Default")
      (node (ref "R25") (pin "1") (pinfunction "1_1") (pintype "passive"))
      (node (ref "R27") (pin "3") (pinfunction "CW_3") (pintype "passive"))
      (node (ref "U5") (pin "2") (pinfunction "IN-_2") (pintype "input"))
    )
    (net (code "25") (name "Net-(R28-CW)") (class "Default")
      (node (ref "R26") (pin "1") (pinfunction "1_1") (pintype "passive"))
      (node (ref "R28") (pin "3") (pinfunction "CW_3") (pintype "passive"))
      (node (ref "U6") (pin "2") (pinfunction "IN-_2") (pintype "input"))
    )
    (net (code "26") (name "Net-(U1-IN+)") (class "Default")
      (node (ref "C1") (pin "1") (pinfunction "1_1") (pintype "passive"))
      (node (ref "L1") (pin "1") (pinfunction "1_1") (pintype "passive"))
      (node (ref "R1") (pin "1") (pinfunction "1_1") (pintype "passive"))
      (node (ref "U1") (pin "3") (pinfunction "IN+_3") (pintype "input"))
    )
    (net (code "27") (name "Net-(U1-IN-)") (class "Default")
      (node (ref "R3") (pin "2") (pinfunction "2_2") (pintype "passive"))
      (node (ref "U1") (pin "2") (pinfunction "IN-_2") (pintype "input"))
      (node (ref "U1") (pin "6") (pinfunction "OUT_6") (pintype "output"))
    )
    (net (code "28") (name "Net-(U2-IN+)") (class "Default")
      (node (ref "C2") (pin "1") (pinfunction "1_1") (pintype "passive"))
      (node (ref "L2") (pin "1") (pinfunction "1_1") (pintype "passive"))
      (node (ref "R2") (pin "1") (pinfunction "1_1") (pintype "passive"))
      (node (ref "U2") (pin "3") (pinfunction "IN+_3") (pintype "input"))
    )
    (net (code "29") (name "Net-(U2-IN-)") (class "Default")
      (node (ref "R4") (pin "2") (pinfunction "2_2") (pintype "passive"))
      (node (ref "U2") (pin "2") (pinfunction "IN-_2") (pintype "input"))
      (node (ref "U2") (pin "6") (pinfunction "OUT_6") (pintype "output"))
    )
    (net (code "30") (name "Net-(U5-IN+)") (class "Default")
      (node (ref "C5") (pin "1") (pinfunction "1_1") (pintype "passive"))
      (node (ref "L5") (pin "1") (pinfunction "1_1") (pintype "passive"))
      (node (ref "R23") (pin "1") (pinfunction "1_1") (pintype "passive"))
      (node (ref "U5") (pin "3") (pinfunction "IN+_3") (pintype "input"))
    )
    (net (code "31") (name "Net-(U6-IN+)") (class "Default")
      (node (ref "C6") (pin "1") (pinfunction "1_1") (pintype "passive"))
      (node (ref "L6") (pin "1") (pinfunction "1_1") (pintype "passive"))
      (node (ref "R24") (pin "1") (pinfunction "1_1") (pintype "passive"))
      (node (ref "U6") (pin "3") (pinfunction "IN+_3") (pintype "input"))
    )
    (net (code "32") (name "Net-(U7-IN+)") (class "Default")
      (node (ref "C9") (pin "2") (pinfunction "2_2") (pintype "passive"))
      (node (ref "L7") (pin "1") (pinfunction "1_1") (pintype "passive"))
      (node (ref "U7") (pin "3") (pinfunction "IN+_3") (pintype "passive"))
    )
    (net (code "33") (name "Net-(U7-IN-)") (class "Default")
      (node (ref "C11") (pin "1") (pinfunction "1_1") (pintype "passive"))
      (node (ref "L11") (pin "1") (pinfunction "1_1") (pintype "passive"))
      (node (ref "U7") (pin "4") (pinfunction "IN-_4") (pintype "passive"))
    )
    (net (code "34") (name "Net-(U7-LO+)") (class "Default")
      (node (ref "C15") (pin "2") (pinfunction "2_2") (pintype "passive"))
      (node (ref "U7") (pin "8") (pinfunction "LO+_8") (pintype "passive"))
    )
    (net (code "35") (name "Net-(U7-LO-)") (class "Default")
      (node (ref "C13") (pin "2") (pinfunction "2_2") (pintype "passive"))
      (node (ref "L13") (pin "2") (pinfunction "2_2") (pintype "passive"))
      (node (ref "U7") (pin "1") (pinfunction "LO-_1") (pintype "passive"))
    )
    (net (code "36") (name "Net-(U7-OUT+)") (class "Default")
      (node (ref "C23") (pin "2") (pinfunction "2_2") (pintype "passive"))
      (node (ref "L15") (pin "2") (pinfunction "2_2") (pintype "passive"))
      (node (ref "U7") (pin "6") (pinfunction "OUT+_6") (pintype "passive"))
    )
    (net (code "37") (name "Net-(U7-OUT-)") (class "Default")
      (node (ref "C21") (pin "1") (pinfunction "1_1") (pintype "passive"))
      (node (ref "L17") (pin "2") (pinfunction "2_2") (pintype "passive"))
      (node (ref "U7") (pin "5") (pinfunction "OUT-_5") (pintype "passive"))
    )
    (net (code "38") (name "Net-(U8-IN+)") (class "Default")
      (node (ref "C10") (pin "2") (pinfunction "2_2") (pintype "passive"))
      (node (ref "L8") (pin "1") (pinfunction "1_1") (pintype "passive"))
      (node (ref "U8") (pin "3") (pinfunction "IN+_3") (pintype "passive"))
    )
    (net (code "39") (name "Net-(U8-IN-)") (class "Default")
      (node (ref "C12") (pin "1") (pinfunction "1_1") (pintype "passive"))
      (node (ref "L12") (pin "1") (pinfunction "1_1") (pintype "passive"))
      (node (ref "U8") (pin "4") (pinfunction "IN-_4") (pintype "passive"))
    )
    (net (code "40") (name "Net-(U8-LO+)") (class "Default")
      (node (ref "C16") (pin "2") (pinfunction "2_2") (pintype "passive"))
      (node (ref "U8") (pin "8") (pinfunction "LO+_8") (pintype "passive"))
    )
    (net (code "41") (name "Net-(U8-LO-)") (class "Default")
      (node (ref "C14") (pin "2") (pinfunction "2_2") (pintype "passive"))
      (node (ref "L14") (pin "2") (pinfunction "2_2") (pintype "passive"))
      (node (ref "U8") (pin "1") (pinfunction "LO-_1") (pintype "passive"))
    )
    (net (code "42") (name "Net-(U8-OUT+)") (class "Default")
      (node (ref "C24") (pin "2") (pinfunction "2_2") (pintype "passive"))
      (node (ref "L16") (pin "2") (pinfunction "2_2") (pintype "passive"))
      (node (ref "U8") (pin "6") (pinfunction "OUT+_6") (pintype "passive"))
    )
    (net (code "43") (name "Net-(U8-OUT-)") (class "Default")
      (node (ref "C22") (pin "1") (pinfunction "1_1") (pintype "passive"))
      (node (ref "L18") (pin "2") (pinfunction "2_2") (pintype "passive"))
      (node (ref "U8") (pin "5") (pinfunction "OUT-_5") (pintype "passive"))
    )
    (net (code "44") (name "unconnected-(R13-CCW-Pad1)") (class "Default")
      (node (ref "R13") (pin "1") (pinfunction "CCW_1") (pintype "passive"))
    )
    (net (code "45") (name "unconnected-(R14-CCW-Pad1)") (class "Default")
      (node (ref "R14") (pin "1") (pinfunction "CCW_1") (pintype "passive"))
    )
    (net (code "46") (name "unconnected-(R27-CCW-Pad1)") (class "Default")
      (node (ref "R27") (pin "1") (pinfunction "CCW_1") (pintype "passive"))
    )
    (net (code "47") (name "unconnected-(R28-CCW-Pad1)") (class "Default")
      (node (ref "R28") (pin "1") (pinfunction "CCW_1") (pintype "passive"))
    )
    (net (code "48") (name "unconnected-(U1-Balance-Pad1)") (class "Default")
      (node (ref "U1") (pin "1") (pinfunction "Balance_1") (pintype "passive+no_connect"))
    )
    (net (code "49") (name "unconnected-(U1-Balance-Pad5)") (class "Default")
      (node (ref "U1") (pin "5") (pinfunction "Balance_5") (pintype "passive+no_connect"))
    )
    (net (code "50") (name "unconnected-(U2-Balance-Pad1)") (class "Default")
      (node (ref "U2") (pin "1") (pinfunction "Balance_1") (pintype "passive+no_connect"))
    )
    (net (code "51") (name "unconnected-(U2-Balance-Pad5)") (class "Default")
      (node (ref "U2") (pin "5") (pinfunction "Balance_5") (pintype "passive+no_connect"))
    )
    (net (code "52") (name "unconnected-(U3-Balance-Pad1)") (class "Default")
      (node (ref "U3") (pin "1") (pinfunction "Balance_1") (pintype "passive"))
    )
    (net (code "53") (name "unconnected-(U3-Balance-Pad5)") (class "Default")
      (node (ref "U3") (pin "5") (pinfunction "Balance_5") (pintype "passive"))
    )
    (net (code "54") (name "unconnected-(U4-Balance-Pad1)") (class "Default")
      (node (ref "U4") (pin "1") (pinfunction "Balance_1") (pintype "passive"))
    )
    (net (code "55") (name "unconnected-(U4-Balance-Pad5)") (class "Default")
      (node (ref "U4") (pin "5") (pinfunction "Balance_5") (pintype "passive"))
    )
    (net (code "56") (name "unconnected-(U5-Balance-Pad1)") (class "Default")
      (node (ref "U5") (pin "1") (pinfunction "Balance_1") (pintype "passive+no_connect"))
    )
    (net (code "57") (name "unconnected-(U5-Balance-Pad5)") (class "Default")
      (node (ref "U5") (pin "5") (pinfunction "Balance_5") (pintype "passive+no_connect"))
    )
    (net (code "58") (name "unconnected-(U6-Balance-Pad1)") (class "Default")
      (node (ref "U6") (pin "1") (pinfunction "Balance_1") (pintype "passive+no_connect"))
    )
    (net (code "59") (name "unconnected-(U6-Balance-Pad5)") (class "Default")
      (node (ref "U6") (pin "5") (pinfunction "Balance_5") (pintype "passive+no_connect"))
    )
  )
)
